# ESP12_Adapter.net
KiCad netlist of a schematic drawn in EAGLE
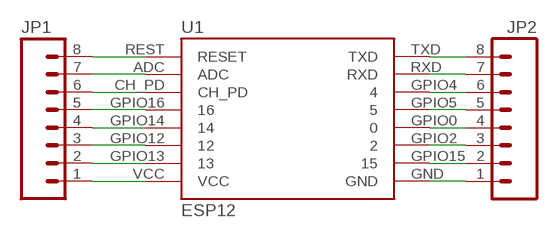
[diagram p0: schematic, sheet 1]

(export (version "E")
  (design (tool "Eeschema 10.0.6"))
  (components
    (comp (ref "JP1")
      (value "M08")
      (footprint "eagle-import:1X08_PIN1_NO_SILK")
      (libsource (lib "eagle-import") (part "M08"))
    )
    (comp (ref "JP2")
      (value "M08")
      (footprint "eagle-import:1X08_PIN1_NO_SILK")
      (libsource (lib "eagle-import") (part "M08"))
    )
    (comp (ref "U1")
      (value "ESP12")
      (footprint "eagle-import:ESP12")
      (libsource (lib "eagle-import") (part "ESP12"))
    )
  )
  (nets
    (net (code "1") (name "Net-(JP1-Pad1)") (class "Default")
      (node (ref "JP1") (pin "1") (pinfunction "1_1") (pintype "passive"))
      (node (ref "U1") (pin "VCC") (pinfunction "VCC_VCC") (pintype "power_in"))
    )
    (net (code "2") (name "Net-(JP1-Pad6)") (class "Default")
      (node (ref "JP1") (pin "6") (pinfunction "6_6") (pintype "passive"))
      (node (ref "U1") (pin "CH_PD") (pinfunction "CH_PD_CH_PD") (pintype "input"))
    )
    (net (code "3") (name "Net-(JP1-Pad7)") (class "Default")
      (node (ref "JP1") (pin "7") (pinfunction "7_7") (pintype "passive"))
      (node (ref "U1") (pin "ADC") (pinfunction "ADC_ADC") (pintype "input"))
    )
    (net (code "4") (name "Net-(JP2-Pad1)") (class "Default")
      (node (ref "JP2") (pin "1") (pinfunction "1_1") (pintype "passive"))
      (node (ref "U1") (pin "GND") (pinfunction "GND_GND") (pintype "power_in"))
    )
    (net (code "5") (name "Net-(JP2-Pad7)") (class "Default")
      (node (ref "JP2") (pin "7") (pinfunction "7_7") (pintype "passive"))
      (node (ref "U1") (pin "RXD") (pinfunction "RXD_RXD") (pintype "output"))
    )
    (net (code "6") (name "Net-(JP2-Pad8)") (class "Default")
      (node (ref "JP2") (pin "8") (pinfunction "8_8") (pintype "passive"))
      (node (ref "U1") (pin "TXD") (pinfunction "TXD_TXD") (pintype "input"))
    )
    (net (code "7") (name "Net-(U1-0)") (class "Default")
      (node (ref "JP2") (pin "4") (pinfunction "4_4") (pintype "passive"))
      (node (ref "U1") (pin "GPIO0") (pinfunction "0_GPIO0") (pintype "bidirectional"))
    )
    (net (code "8") (name "Net-(U1-2)") (class "Default")
      (node (ref "JP2") (pin "3") (pinfunction "3_3") (pintype "passive"))
      (node (ref "U1") (pin "GPIO2") (pinfunction "2_GPIO2") (pintype "bidirectional"))
    )
    (net (code "9") (name "Net-(U1-4)") (class "Default")
      (node (ref "JP2") (pin "6") (pinfunction "6_6") (pintype "passive"))
      (node (ref "U1") (pin "GPIO4") (pinfunction "4_GPIO4") (pintype "bidirectional"))
    )
    (net (code "10") (name "Net-(U1-5)") (class "Default")
      (node (ref "JP2") (pin "5") (pinfunction "5_5") (pintype "passive"))
      (node (ref "U1") (pin "GPIO5") (pinfunction "5_GPIO5") (pintype "bidirectional"))
    )
    (net (code "11") (name "Net-(U1-12)") (class "Default")
      (node (ref "JP1") (pin "3") (pinfunction "3_3") (pintype "passive"))
      (node (ref "U1") (pin "GPIO12") (pinfunction "12_GPIO12") (pintype "bidirectional"))
    )
    (net (code "12") (name "Net-(U1-13)") (class "Default")
      (node (ref "JP1") (pin "2") (pinfunction "2_2") (pintype "passive"))
      (node (ref "U1") (pin "GPIO13") (pinfunction "13_GPIO13") (pintype "bidirectional"))
    )
    (net (code "13") (name "Net-(U1-14)") (class "Default")
      (node (ref "JP1") (pin "4") (pinfunction "4_4") (pintype "passive"))
      (node (ref "U1") (pin "GPIO14") (pinfunction "14_GPIO14") (pintype "bidirectional"))
    )
    (net (code "14") (name "Net-(U1-15)") (class "Default")
      (node (ref "JP2") (pin "2") (pinfunction "2_2") (pintype "passive"))
      (node (ref "U1") (pin "GPIO15") (pinfunction "15_GPIO15") (pintype "bidirectional"))
    )
    (net (code "15") (name "Net-(U1-16)") (class "Default")
      (node (ref "JP1") (pin "5") (pinfunction "5_5") (pintype "passive"))
      (node (ref "U1") (pin "GPIO16") (pinfunction "16_GPIO16") (pintype "bidirectional"))
    )
    (net (code "16") (name "Net-(U1-RESET)") (class "Default")
      (node (ref "JP1") (pin "8") (pinfunction "8_8") (pintype "passive"))
      (node (ref "U1") (pin "REST") (pinfunction "RESET_REST") (pintype "input"))
    )
  )
)
